# uv-exposure-box-display-v2.net
KiCad netlist of a schematic drawn in EAGLE
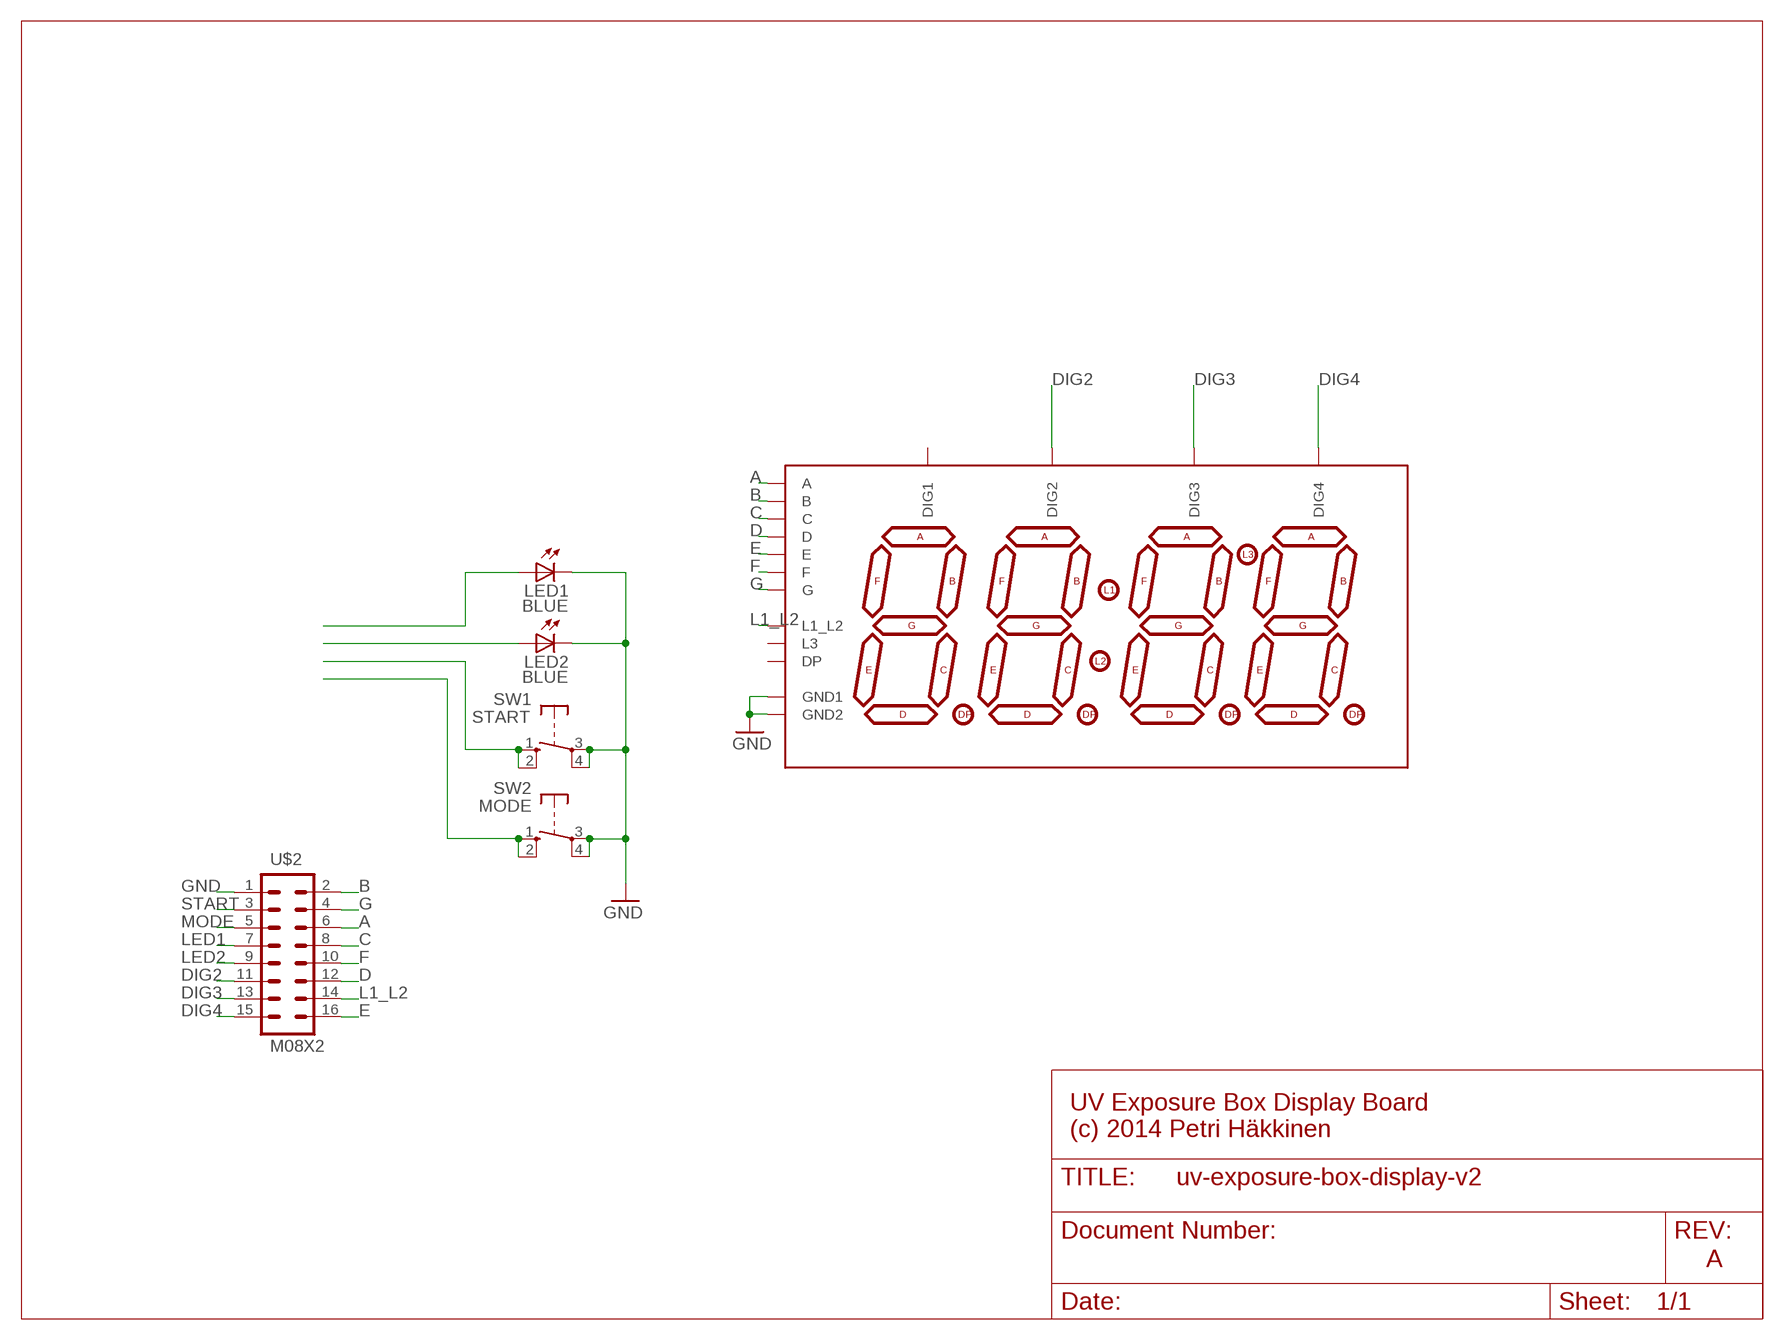
[diagram p0: schematic, sheet 1]

(export (version "E")
  (design (tool "Eeschema 10.0.6"))
  (components
    (comp (ref "LED1")
      (value "BLUE")
      (footprint "eagle-import:LED3MM")
      (libsource (lib "eagle-import") (part "LED3MM"))
    )
    (comp (ref "LED2")
      (value "BLUE")
      (footprint "eagle-import:LED3MM")
      (libsource (lib "eagle-import") (part "LED3MM"))
    )
    (comp (ref "SW1")
      (value "START")
      (footprint "eagle-import:DTE6K")
      (libsource (lib "eagle-import") (part "DTE6K"))
    )
    (comp (ref "SW2")
      (value "MODE")
      (footprint "eagle-import:DTE6K")
      (libsource (lib "eagle-import") (part "DTE6K"))
    )
    (comp (ref "U$1")
      (value "7-SEGMENT-4DIGIT")
      (footprint "eagle-import:7-SEGMENT-4DIGIT-YOUNGSUN")
      (libsource (lib "eagle-import") (part "7-SEGMENT-4DIGIT"))
    )
    (comp (ref "U$2")
      (value "M08X2")
      (footprint "eagle-import:2X8")
      (libsource (lib "eagle-import") (part "M08X2"))
    )
  )
  (nets
    (net (code "1") (name "/A") (class "Default")
      (node (ref "U$1") (pin "14") (pinfunction "A_14") (pintype "bidirectional"))
      (node (ref "U$2") (pin "6") (pinfunction "6_6") (pintype "passive"))
    )
    (net (code "2") (name "/B") (class "Default")
      (node (ref "U$1") (pin "16") (pinfunction "B_16") (pintype "bidirectional"))
      (node (ref "U$2") (pin "2") (pinfunction "2_2") (pintype "passive"))
    )
    (net (code "3") (name "/C") (class "Default")
      (node (ref "U$1") (pin "13") (pinfunction "C_13") (pintype "bidirectional"))
      (node (ref "U$2") (pin "8") (pinfunction "8_8") (pintype "passive"))
    )
    (net (code "4") (name "/D") (class "Default")
      (node (ref "U$1") (pin "3") (pinfunction "D_3") (pintype "bidirectional"))
      (node (ref "U$2") (pin "12") (pinfunction "12_12") (pintype "passive"))
    )
    (net (code "5") (name "/DIG2") (class "Default")
      (node (ref "U$1") (pin "2") (pinfunction "DIG2_2") (pintype "bidirectional"))
      (node (ref "U$2") (pin "11") (pinfunction "11_11") (pintype "passive"))
    )
    (net (code "6") (name "/DIG3") (class "Default")
      (node (ref "U$1") (pin "6") (pinfunction "DIG3_6") (pintype "bidirectional"))
      (node (ref "U$2") (pin "13") (pinfunction "13_13") (pintype "passive"))
    )
    (net (code "7") (name "/DIG4") (class "Default")
      (node (ref "U$1") (pin "8") (pinfunction "DIG4_8") (pintype "bidirectional"))
      (node (ref "U$2") (pin "15") (pinfunction "15_15") (pintype "passive"))
    )
    (net (code "8") (name "/E") (class "Default")
      (node (ref "U$1") (pin "5") (pinfunction "E_5") (pintype "bidirectional"))
      (node (ref "U$2") (pin "16") (pinfunction "16_16") (pintype "passive"))
    )
    (net (code "9") (name "/F") (class "Default")
      (node (ref "U$1") (pin "11") (pinfunction "F_11") (pintype "bidirectional"))
      (node (ref "U$2") (pin "10") (pinfunction "10_10") (pintype "passive"))
    )
    (net (code "10") (name "/G") (class "Default")
      (node (ref "U$1") (pin "15") (pinfunction "G_15") (pintype "bidirectional"))
      (node (ref "U$2") (pin "4") (pinfunction "4_4") (pintype "passive"))
    )
    (net (code "11") (name "/L1_L2") (class "Default")
      (node (ref "U$1") (pin "4") (pinfunction "L1_L2_4") (pintype "bidirectional"))
      (node (ref "U$2") (pin "14") (pinfunction "14_14") (pintype "passive"))
    )
    (net (code "12") (name "/LED1") (class "Default")
      (node (ref "LED1") (pin "A") (pinfunction "A_A") (pintype "passive"))
      (node (ref "U$2") (pin "7") (pinfunction "7_7") (pintype "passive"))
    )
    (net (code "13") (name "/LED2") (class "Default")
      (node (ref "LED2") (pin "A") (pinfunction "A_A") (pintype "passive"))
      (node (ref "U$2") (pin "9") (pinfunction "9_9") (pintype "passive"))
    )
    (net (code "14") (name "/MODE") (class "Default")
      (node (ref "SW2") (pin "1") (pinfunction "S_1") (pintype "passive"))
      (node (ref "SW2") (pin "2") (pinfunction "S_2") (pintype "passive"))
      (node (ref "U$2") (pin "5") (pinfunction "5_5") (pintype "passive"))
    )
    (net (code "15") (name "/START") (class "Default")
      (node (ref "SW1") (pin "1") (pinfunction "S_1") (pintype "passive"))
      (node (ref "SW1") (pin "2") (pinfunction "S_2") (pintype "passive"))
      (node (ref "U$2") (pin "3") (pinfunction "3_3") (pintype "passive"))
    )
    (net (code "16") (name "GND") (class "Default")
      (node (ref "LED1") (pin "K") (pinfunction "C_K") (pintype "passive"))
      (node (ref "LED2") (pin "K") (pinfunction "C_K") (pintype "passive"))
      (node (ref "SW1") (pin "3") (pinfunction "P_3") (pintype "passive"))
      (node (ref "SW1") (pin "4") (pinfunction "P_4") (pintype "passive"))
      (node (ref "SW2") (pin "3") (pinfunction "P_3") (pintype "passive"))
      (node (ref "SW2") (pin "4") (pinfunction "P_4") (pintype "passive"))
      (node (ref "U$1") (pin "12") (pinfunction "GND2_12") (pintype "bidirectional"))
      (node (ref "U$1") (pin "9") (pinfunction "GND1_9") (pintype "bidirectional"))
      (node (ref "U$2") (pin "1") (pinfunction "1_1") (pintype "passive"))
    )
    (net (code "17") (name "unconnected-(U$1-DIG1-Pad1)") (class "Default")
      (node (ref "U$1") (pin "1") (pinfunction "DIG1_1") (pintype "bidirectional"))
    )
    (net (code "18") (name "unconnected-(U$1-DP-Pad7)") (class "Default")
      (node (ref "U$1") (pin "7") (pinfunction "DP_7") (pintype "bidirectional"))
    )
    (net (code "19") (name "unconnected-(U$1-L3-Pad10)") (class "Default")
      (node (ref "U$1") (pin "10") (pinfunction "L3_10") (pintype "bidirectional"))
    )
  )
)
